# ROLETA2-A1-P01.net
KiCad netlist of a schematic drawn in Altium Designer
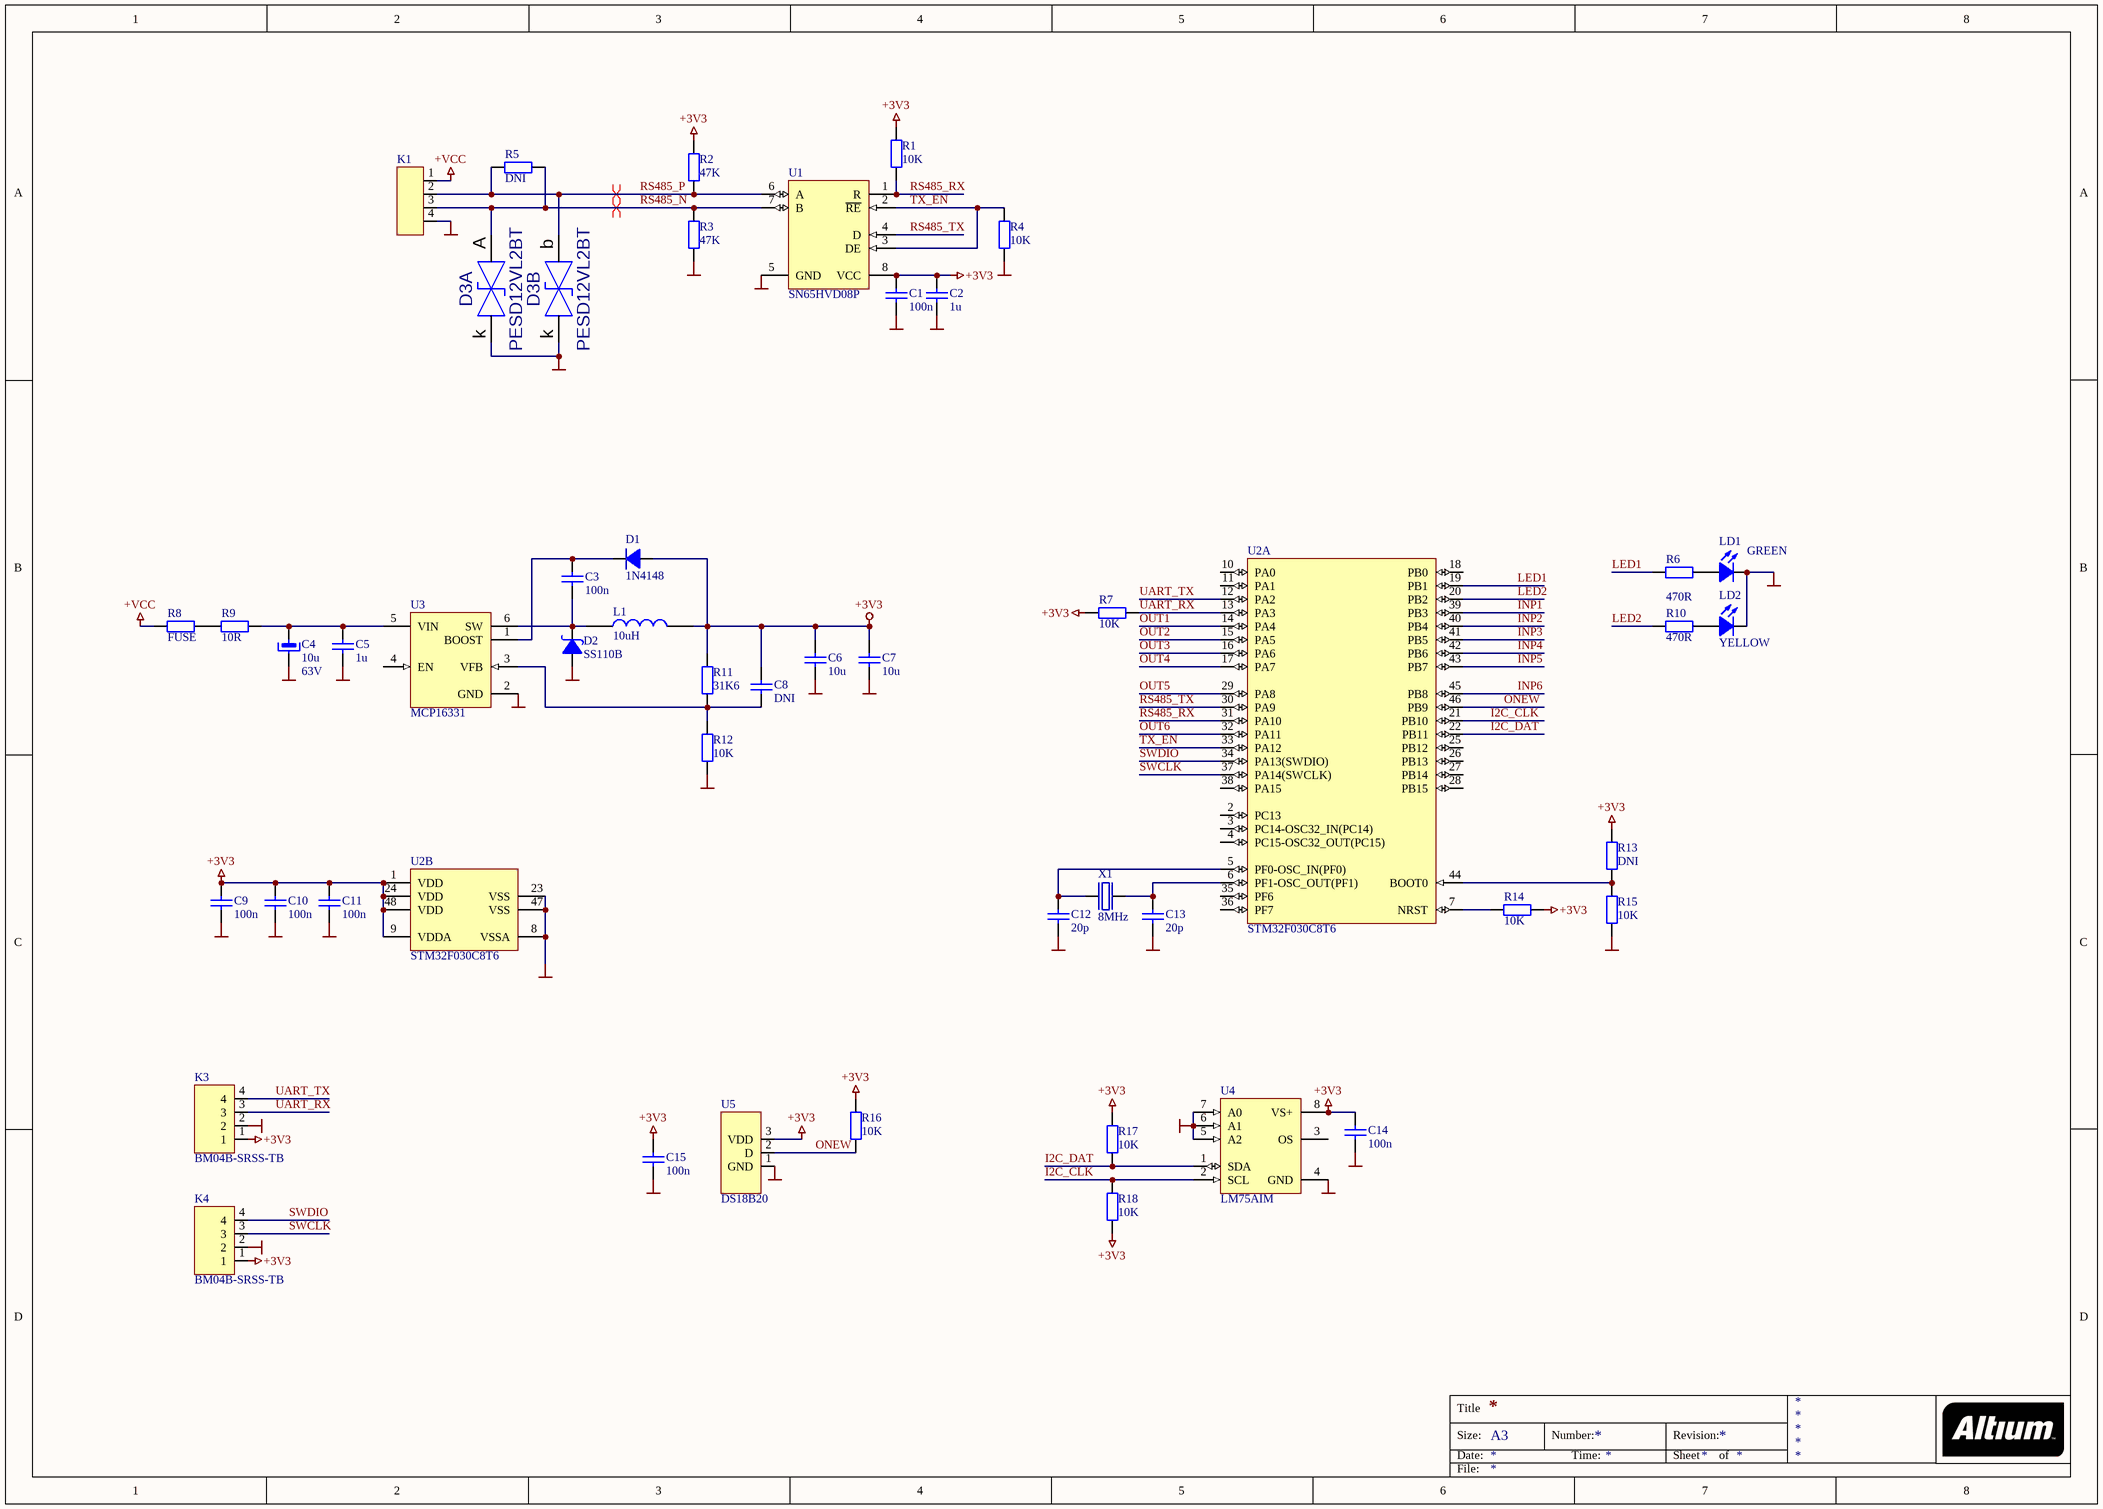
[diagram p0: ROLETA2-A1-P01.SchDoc]

(export (version "E")
  (design (tool "Eeschema 10.0.6"))
  (components
    (comp (ref "C1")
      (value "100n")
      (footprint "Passive:CC0805-1")
      (description "Capacitor chip ceramic 0805")
      (libsource (lib "CapChipCer") (part "CAPCC0805_1U50VX7R"))
    )
    (comp (ref "C2")
      (value "1u")
      (footprint "Passive:CC0805-1")
      (description "Capacitor chip ceramic 0805")
      (libsource (lib "CapChipCer") (part "CAPCC0805_1U50VX7R"))
    )
    (comp (ref "C3")
      (value "100n")
      (footprint "Passive:CC0805-1")
      (description "Capacitor chip ceramic 0805")
      (libsource (lib "CapChipCer") (part "CAPCC0805_1U50VX7R"))
    )
    (comp (ref "C4")
      (value "10u")
      (footprint "CAPPS-D6.3X7.7")
      (description "Capacitor electrolitic SMD 6.3X6.3X7.7MM low ESR")
      (fields (field (name "COMMENT2") "63V"))
      (libsource (lib "CapElectTht") (part "CAPPS100U25VFP"))
    )
    (comp (ref "C5")
      (value "1u")
      (footprint "Passive:CC0805-1")
      (description "Capacitor chip ceramic 0805")
      (libsource (lib "CapChipCer") (part "CAPCC0805_1U50VX7R"))
    )
    (comp (ref "C6")
      (value "10u")
      (footprint "CC0805-1")
      (description "Capacitor chip ceramic 0805")
      (libsource (lib "CapChipCer") (part "CAPCC0805_10U16VX5R"))
    )
    (comp (ref "C7")
      (value "10u")
      (footprint "CC0805-1")
      (description "Capacitor chip ceramic 0805")
      (libsource (lib "CapChipCer") (part "CAPCC0805_10U16VX5R"))
    )
    (comp (ref "C8")
      (value "DNI")
      (footprint "Passive:CC0805-1")
      (description "Capacitor chip ceramic 0805")
      (libsource (lib "CapChipCer") (part "CAPCC0805_1U50VX7R"))
    )
    (comp (ref "C9")
      (value "100n")
      (footprint "CC0805-1")
      (description "Capacitor chip ceramic 0805")
      (libsource (lib "CapChipCer") (part "CAPCC0805_100N50VX7R"))
    )
    (comp (ref "C10")
      (value "100n")
      (footprint "CC0805-1")
      (description "Capacitor chip ceramic 0805")
      (libsource (lib "CapChipCer") (part "CAPCC0805_100N50VX7R"))
    )
    (comp (ref "C11")
      (value "100n")
      (footprint "CC0805-1")
      (description "Capacitor chip ceramic 0805")
      (libsource (lib "CapChipCer") (part "CAPCC0805_100N50VX7R"))
    )
    (comp (ref "C12")
      (value "20p")
      (footprint "CC0805-1")
      (description "Capacitor chip ceramic 0805")
      (libsource (lib "CapChipCer") (part "CAPCC0805_100N50VX7R"))
    )
    (comp (ref "C13")
      (value "20p")
      (footprint "CC0805-1")
      (description "Capacitor chip ceramic 0805")
      (libsource (lib "CapChipCer") (part "CAPCC0805_100N50VX7R"))
    )
    (comp (ref "C14")
      (value "100n")
      (footprint "CC0805-1")
      (description "Capacitor chip ceramic 0805")
      (libsource (lib "CapChipCer") (part "CAPCC0805_100N50VX7R"))
    )
    (comp (ref "C15")
      (value "100n")
      (footprint "CC0805-1")
      (description "Capacitor chip ceramic 0805")
      (libsource (lib "CapChipCer") (part "CAPCC0805_100N50VX7R"))
    )
    (comp (ref "D1")
      (value "1N4148")
      (footprint "Active:SOD323")
      (description "Small Signal Diode")
      (fields (field (name "MANUFACTURER") "Vishay"))
      (libsource (lib "Discrete") (part "D-1N4148WS"))
    )
    (comp (ref "D2")
      (value "SS110B")
      (footprint "Passive:DO-214AC")
      (description "Schottky Diode")
      (fields (field (name "MANUFACTURER") "multicomp"))
      (libsource (lib "Discrete") (part "CD214A-B240LF-0.3V@1A"))
    )
    (comp (ref "D3")
      (value "PESD12VL2BT")
      (footprint "SOT-23_NUP2105L(Primary)")
      (description "Diode")
      (libsource (lib "fractal_lib") (part "NUP2105L"))
    )
    (comp (ref "K1")
      (value "Terminal Block Connector, 3.81mm, Right Angle")
      (footprint "CONN_3.81_4")
      (description "Terminal Block Connector, 3.81mm, 4pin")
      (libsource (lib "fractal_lib") (part "CONN_TB_3.81_4PIN"))
    )
    (comp (ref "K3")
      (value "BM04B-SRSS-TB")
      (footprint "JST-SH-4pin")
      (description "JST connector 4pin vertical")
      (libsource (lib "fractal_lib") (part "JST-SH-BM04B-SRSS-TB"))
    )
    (comp (ref "K4")
      (value "BM04B-SRSS-TB")
      (footprint "JST-SH-4pin")
      (description "JST connector 4pin vertical")
      (libsource (lib "fractal_lib") (part "JST-SH-BM04B-SRSS-TB"))
    )
    (comp (ref "L1")
      (value "10uH")
      (footprint "IND-LQH32CN4R7M33l")
      (description "Chip Inductor 4 x 4 mm")
      (fields (field (name "MANUFACTURER") "Murata"))
      (libsource (lib "Induct") (part "LQH44PN100MP0L"))
    )
    (comp (ref "LD1")
      (value "GREEN")
      (footprint "Active:LEDGREENC190")
      (description "LED green HSMG vertical")
      (fields (field (name "MANUFACTURER") "Avago"))
      (libsource (lib "Discrete") (part "LED-GREEN0603V"))
    )
    (comp (ref "LD2")
      (value "YELLOW")
      (footprint "Active:LEDYELLOWC190")
      (description "LED yellow HSMY vertical")
      (fields (field (name "MANUFACTURER") "Avago"))
      (libsource (lib "Discrete") (part "LED-YELLOW0603V"))
    )
    (comp (ref "R1")
      (value "10K")
      (footprint "RC0805-1")
      (description "Chip Resistor 0805")
      (libsource (lib "") (part "RES0805_1"))
    )
    (comp (ref "R2")
      (value "47K")
      (footprint "RC0805-1")
      (description "Chip Resistor 0805")
      (libsource (lib "Resistors") (part "RES0805"))
    )
    (comp (ref "R3")
      (value "47K")
      (footprint "RC0805-1")
      (description "Chip Resistor 0805")
      (libsource (lib "Resistors") (part "RES0805"))
    )
    (comp (ref "R4")
      (value "10K")
      (footprint "RC0805-1")
      (description "Chip Resistor 0805")
      (libsource (lib "") (part "RES0805_1"))
    )
    (comp (ref "R5")
      (value "DNI")
      (footprint "RC0805-1")
      (description "Chip Resistor 0805")
      (libsource (lib "") (part "RES0805_1"))
    )
    (comp (ref "R6")
      (value "470R")
      (footprint "RC0805-1")
      (description "Chip Resistor 0805")
      (libsource (lib "") (part "RES0805_1"))
    )
    (comp (ref "R7")
      (value "10K")
      (footprint "RC0805-1")
      (description "Chip Resistor 0805")
      (libsource (lib "") (part "RES0805_1"))
    )
    (comp (ref "R8")
      (value "FUSE")
      (footprint "RC1206-1")
      (description "Chip Resistor 1206")
      (libsource (lib "Resistors") (part "RES1206"))
    )
    (comp (ref "R9")
      (value "10R")
      (footprint "RC0805-1")
      (description "Chip Resistor 0805")
      (libsource (lib "") (part "RES0805_3"))
    )
    (comp (ref "R10")
      (value "470R")
      (footprint "RC0805-1")
      (description "Chip Resistor 0805")
      (libsource (lib "") (part "RES0805_1"))
    )
    (comp (ref "R11")
      (value "31K6")
      (footprint "RC0805-1")
      (description "Chip Resistor 0805")
      (libsource (lib "Resistors") (part "RES0805"))
    )
    (comp (ref "R12")
      (value "10K")
      (footprint "RC0805-1")
      (description "Chip Resistor 0805")
      (libsource (lib "Resistors") (part "RES0805"))
    )
    (comp (ref "R13")
      (value "DNI")
      (footprint "RC0805-1")
      (description "Chip Resistor 0805")
      (libsource (lib "Resistors") (part "RES0805"))
    )
    (comp (ref "R14")
      (value "10K")
      (footprint "RC0805-1")
      (description "Chip Resistor 0805")
      (libsource (lib "") (part "RES0805_3"))
    )
    (comp (ref "R15")
      (value "10K")
      (footprint "RC0805-1")
      (description "Chip Resistor 0805")
      (libsource (lib "") (part "RES0805_2"))
    )
    (comp (ref "R16")
      (value "10K")
      (footprint "RC0805-1")
      (description "Chip Resistor 0805")
      (libsource (lib "") (part "RES0805_2"))
    )
    (comp (ref "R17")
      (value "10K")
      (footprint "RC0805-1")
      (description "Chip Resistor 0805")
      (libsource (lib "") (part "RES0805_2"))
    )
    (comp (ref "R18")
      (value "10K")
      (footprint "RC0805-1")
      (description "Chip Resistor 0805")
      (libsource (lib "Resistors") (part "RES0805"))
    )
    (comp (ref "U1")
      (value "SN65HVD08P")
      (footprint "P8")
      (description "3.3 / 5 V RS-485 Transceiver, 10 Mbps, Half Duplex, -40 to 85 degC, 8-pin PDIP (P), Pb-Free (RoHS)")
      (fields (field (name "MANUFACTURER") "Texas Instruments"))
      (libsource (lib "fractal_lib") (part "SN65HVD08P"))
    )
    (comp (ref "U2")
      (value "STM32F030C8T6")
      (footprint "STM-LQFP48_N")
      (libsource (lib "fractal_lib") (part "STM32F030C8T6"))
    )
    (comp (ref "U3")
      (value "MCP16331")
      (footprint "MCHP-SOT-23-CH6_N")
      (fields (field (name "MANUFACTURER") "Microchip") (field (name "PARTNUMBER") "MCP16301T-E/CH"))
      (libsource (lib "fractal_lib") (part "MCP16301T-E/CH"))
    )
    (comp (ref "U4")
      (value "LM75AIM")
      (footprint "M08A_N")
      (description "Digital Temperature Sensor and Thermal Watchdog with Two-Wire Interface, 8-pin Narrow SOIC")
      (fields (field (name "MANUFACTURER") "National Semiconductor"))
      (libsource (lib "fractal_lib") (part "LM75AIM"))
    )
    (comp (ref "U5")
      (value "DS18B20")
      (footprint "TO92")
      (description "digital temperature sensor")
      (libsource (lib "fractal_lib") (part "DS18B20"))
    )
    (comp (ref "X1")
      (value "8MHz")
      (footprint "OSCCC150X320X9-2N")
      (description "SMD Crystal 8MHz")
      (libsource (lib "fractal_lib") (part "XTAL-SMD_8MHz"))
    )
  )
  (nets
    (net (code "1") (name "+3V3") (class "Default")
      (node (ref "C1") (pin "2") (pinfunction "2_2") (pintype "passive"))
      (node (ref "C10") (pin "2") (pinfunction "2_2") (pintype "passive"))
      (node (ref "C11") (pin "2") (pinfunction "2_2") (pintype "passive"))
      (node (ref "C14") (pin "2") (pinfunction "2_2") (pintype "passive"))
      (node (ref "C15") (pin "2") (pinfunction "2_2") (pintype "passive"))
      (node (ref "C2") (pin "2") (pinfunction "2_2") (pintype "passive"))
      (node (ref "C6") (pin "2") (pinfunction "2_2") (pintype "passive"))
      (node (ref "C7") (pin "2") (pinfunction "2_2") (pintype "passive"))
      (node (ref "C8") (pin "2") (pinfunction "2_2") (pintype "passive"))
      (node (ref "C9") (pin "2") (pinfunction "2_2") (pintype "passive"))
      (node (ref "D1") (pin "2") (pinfunction "A_2") (pintype "passive"))
      (node (ref "K3") (pin "1") (pinfunction "1_1") (pintype "passive"))
      (node (ref "K4") (pin "1") (pinfunction "1_1") (pintype "passive"))
      (node (ref "L1") (pin "2") (pinfunction "2_2") (pintype "passive"))
      (node (ref "R1") (pin "2") (pinfunction "2_2") (pintype "passive"))
      (node (ref "R11") (pin "2") (pinfunction "2_2") (pintype "passive"))
      (node (ref "R13") (pin "2") (pinfunction "2_2") (pintype "passive"))
      (node (ref "R14") (pin "1") (pinfunction "1_1") (pintype "passive"))
      (node (ref "R16") (pin "1") (pinfunction "1_1") (pintype "passive"))
      (node (ref "R17") (pin "1") (pinfunction "1_1") (pintype "passive"))
      (node (ref "R18") (pin "1") (pinfunction "1_1") (pintype "passive"))
      (node (ref "R2") (pin "2") (pinfunction "2_2") (pintype "passive"))
      (node (ref "R7") (pin "1") (pinfunction "1_1") (pintype "passive"))
      (node (ref "U1") (pin "8") (pinfunction "VCC_8") (pintype "power_in"))
      (node (ref "U2") (pin "1") (pinfunction "VDD_1") (pintype "power_in"))
      (node (ref "U2") (pin "24") (pinfunction "VDD_24") (pintype "power_in"))
      (node (ref "U2") (pin "48") (pinfunction "VDD_48") (pintype "power_in"))
      (node (ref "U2") (pin "9") (pinfunction "VDDA_9") (pintype "power_in"))
      (node (ref "U4") (pin "8") (pinfunction "VS+_8") (pintype "power_in"))
      (node (ref "U5") (pin "3") (pinfunction "VDD_3") (pintype "passive"))
    )
    (net (code "2") (name "+VCC") (class "Default")
      (node (ref "K1") (pin "1") (pinfunction "A_1") (pintype "passive"))
      (node (ref "R8") (pin "1") (pinfunction "1_1") (pintype "passive"))
    )
    (net (code "3") (name "/I2C_CLK") (class "Default")
      (node (ref "R18") (pin "2") (pinfunction "2_2") (pintype "passive"))
      (node (ref "U2") (pin "21") (pinfunction "PB10_21") (pintype "bidirectional"))
      (node (ref "U4") (pin "2") (pinfunction "SCL_2") (pintype "input"))
    )
    (net (code "4") (name "/I2C_DAT") (class "Default")
      (node (ref "R17") (pin "2") (pinfunction "2_2") (pintype "passive"))
      (node (ref "U2") (pin "22") (pinfunction "PB11_22") (pintype "bidirectional"))
      (node (ref "U4") (pin "1") (pinfunction "SDA_1") (pintype "bidirectional"))
    )
    (net (code "5") (name "/INP1") (class "Default")
      (node (ref "U2") (pin "39") (pinfunction "PB3_39") (pintype "bidirectional"))
    )
    (net (code "6") (name "/INP2") (class "Default")
      (node (ref "U2") (pin "40") (pinfunction "PB4_40") (pintype "bidirectional"))
    )
    (net (code "7") (name "/INP3") (class "Default")
      (node (ref "U2") (pin "41") (pinfunction "PB5_41") (pintype "bidirectional"))
    )
    (net (code "8") (name "/INP4") (class "Default")
      (node (ref "U2") (pin "42") (pinfunction "PB6_42") (pintype "bidirectional"))
    )
    (net (code "9") (name "/INP5") (class "Default")
      (node (ref "U2") (pin "43") (pinfunction "PB7_43") (pintype "bidirectional"))
    )
    (net (code "10") (name "/INP6") (class "Default")
      (node (ref "U2") (pin "45") (pinfunction "PB8_45") (pintype "bidirectional"))
    )
    (net (code "11") (name "/LED1") (class "Default")
      (node (ref "R6") (pin "1") (pinfunction "1_1") (pintype "passive"))
      (node (ref "U2") (pin "19") (pinfunction "PB1_19") (pintype "bidirectional"))
    )
    (net (code "12") (name "/LED2") (class "Default")
      (node (ref "R10") (pin "1") (pinfunction "1_1") (pintype "passive"))
      (node (ref "U2") (pin "20") (pinfunction "PB2_20") (pintype "bidirectional"))
    )
    (net (code "13") (name "/ONEW") (class "Default")
      (node (ref "R16") (pin "2") (pinfunction "2_2") (pintype "passive"))
      (node (ref "U2") (pin "46") (pinfunction "PB9_46") (pintype "bidirectional"))
      (node (ref "U5") (pin "2") (pinfunction "D_2") (pintype "passive"))
    )
    (net (code "14") (name "/OUT1") (class "Default")
      (node (ref "U2") (pin "14") (pinfunction "PA4_14") (pintype "bidirectional"))
    )
    (net (code "15") (name "/OUT2") (class "Default")
      (node (ref "U2") (pin "15") (pinfunction "PA5_15") (pintype "bidirectional"))
    )
    (net (code "16") (name "/OUT3") (class "Default")
      (node (ref "U2") (pin "16") (pinfunction "PA6_16") (pintype "bidirectional"))
    )
    (net (code "17") (name "/OUT4") (class "Default")
      (node (ref "U2") (pin "17") (pinfunction "PA7_17") (pintype "bidirectional"))
    )
    (net (code "18") (name "/OUT5") (class "Default")
      (node (ref "U2") (pin "29") (pinfunction "PA8_29") (pintype "bidirectional"))
    )
    (net (code "19") (name "/OUT6") (class "Default")
      (node (ref "U2") (pin "32") (pinfunction "PA11_32") (pintype "bidirectional"))
    )
    (net (code "20") (name "/RS485_N") (class "Default")
      (node (ref "D3") (pin "A") (pinfunction "A_A") (pintype "passive"))
      (node (ref "K1") (pin "3") (pinfunction "A_3") (pintype "passive"))
      (node (ref "R3") (pin "2") (pinfunction "2_2") (pintype "passive"))
      (node (ref "R5") (pin "2") (pinfunction "2_2") (pintype "passive"))
      (node (ref "U1") (pin "7") (pinfunction "B_7") (pintype "bidirectional"))
    )
    (net (code "21") (name "/RS485_P") (class "Default")
      (node (ref "D3") (pin "b") (pinfunction "A_b") (pintype "passive"))
      (node (ref "K1") (pin "2") (pinfunction "K_2") (pintype "passive"))
      (node (ref "R2") (pin "1") (pinfunction "1_1") (pintype "passive"))
      (node (ref "R5") (pin "1") (pinfunction "1_1") (pintype "passive"))
      (node (ref "U1") (pin "6") (pinfunction "A_6") (pintype "bidirectional"))
    )
    (net (code "22") (name "/RS485_RX") (class "Default")
      (node (ref "R1") (pin "1") (pinfunction "1_1") (pintype "passive"))
      (node (ref "U1") (pin "1") (pinfunction "R_1") (pintype "tri_state"))
      (node (ref "U2") (pin "31") (pinfunction "PA10_31") (pintype "bidirectional"))
    )
    (net (code "23") (name "/RS485_TX") (class "Default")
      (node (ref "U1") (pin "4") (pinfunction "D_4") (pintype "input"))
      (node (ref "U2") (pin "30") (pinfunction "PA9_30") (pintype "bidirectional"))
    )
    (net (code "24") (name "/SWCLK") (class "Default")
      (node (ref "K4") (pin "3") (pinfunction "3_3") (pintype "passive"))
      (node (ref "U2") (pin "37") (pinfunction "PA14(SWCLK)_37") (pintype "bidirectional"))
    )
    (net (code "25") (name "/SWDIO") (class "Default")
      (node (ref "K4") (pin "4") (pinfunction "4_4") (pintype "passive"))
      (node (ref "U2") (pin "34") (pinfunction "PA13(SWDIO)_34") (pintype "bidirectional"))
    )
    (net (code "26") (name "/TX_EN") (class "Default")
      (node (ref "R4") (pin "2") (pinfunction "2_2") (pintype "passive"))
      (node (ref "U1") (pin "2") (pinfunction "~{RE}_2") (pintype "input"))
      (node (ref "U1") (pin "3") (pinfunction "DE_3") (pintype "input"))
      (node (ref "U2") (pin "33") (pinfunction "PA12_33") (pintype "bidirectional"))
    )
    (net (code "27") (name "/UART_RX") (class "Default")
      (node (ref "K3") (pin "3") (pinfunction "3_3") (pintype "passive"))
      (node (ref "R7") (pin "2") (pinfunction "2_2") (pintype "passive"))
      (node (ref "U2") (pin "13") (pinfunction "PA3_13") (pintype "bidirectional"))
    )
    (net (code "28") (name "/UART_TX") (class "Default")
      (node (ref "K3") (pin "4") (pinfunction "4_4") (pintype "passive"))
      (node (ref "U2") (pin "12") (pinfunction "PA2_12") (pintype "bidirectional"))
    )
    (net (code "29") (name "GND") (class "Default")
      (node (ref "C1") (pin "1") (pinfunction "1_1") (pintype "passive"))
      (node (ref "C10") (pin "1") (pinfunction "1_1") (pintype "passive"))
      (node (ref "C11") (pin "1") (pinfunction "1_1") (pintype "passive"))
      (node (ref "C12") (pin "1") (pinfunction "1_1") (pintype "passive"))
      (node (ref "C13") (pin "1") (pinfunction "1_1") (pintype "passive"))
      (node (ref "C14") (pin "1") (pinfunction "1_1") (pintype "passive"))
      (node (ref "C15") (pin "1") (pinfunction "1_1") (pintype "passive"))
      (node (ref "C2") (pin "1") (pinfunction "1_1") (pintype "passive"))
      (node (ref "C4") (pin "2") (pinfunction "2_2") (pintype "passive"))
      (node (ref "C5") (pin "1") (pinfunction "1_1") (pintype "passive"))
      (node (ref "C6") (pin "1") (pinfunction "1_1") (pintype "passive"))
      (node (ref "C7") (pin "1") (pinfunction "1_1") (pintype "passive"))
      (node (ref "C9") (pin "1") (pinfunction "1_1") (pintype "passive"))
      (node (ref "D2") (pin "A") (pinfunction "A_A") (pintype "passive"))
      (node (ref "D3") (pin "k") (pinfunction "K_k") (pintype "power_in"))
      (node (ref "K1") (pin "4") (pinfunction "K_4") (pintype "passive"))
      (node (ref "K3") (pin "2") (pinfunction "2_2") (pintype "passive"))
      (node (ref "K4") (pin "2") (pinfunction "2_2") (pintype "passive"))
      (node (ref "LD1") (pin "1") (pinfunction "C_1") (pintype "passive"))
      (node (ref "LD2") (pin "1") (pinfunction "C_1") (pintype "passive"))
      (node (ref "R12") (pin "1") (pinfunction "1_1") (pintype "passive"))
      (node (ref "R15") (pin "2") (pinfunction "2_2") (pintype "passive"))
      (node (ref "R3") (pin "1") (pinfunction "1_1") (pintype "passive"))
      (node (ref "R4") (pin "1") (pinfunction "1_1") (pintype "passive"))
      (node (ref "U1") (pin "5") (pinfunction "GND_5") (pintype "power_in"))
      (node (ref "U2") (pin "23") (pinfunction "VSS_23") (pintype "power_in"))
      (node (ref "U2") (pin "47") (pinfunction "VSS_47") (pintype "power_in"))
      (node (ref "U2") (pin "8") (pinfunction "VSSA_8") (pintype "power_in"))
      (node (ref "U3") (pin "2") (pinfunction "GND_2") (pintype "power_in"))
      (node (ref "U4") (pin "4") (pinfunction "GND_4") (pintype "power_in"))
      (node (ref "U4") (pin "5") (pinfunction "A2_5") (pintype "input"))
      (node (ref "U4") (pin "6") (pinfunction "A1_6") (pintype "input"))
      (node (ref "U4") (pin "7") (pinfunction "A0_7") (pintype "input"))
      (node (ref "U5") (pin "1") (pinfunction "GND_1") (pintype "passive"))
    )
    (net (code "30") (name "Net-(D1-C)") (class "Default")
      (node (ref "C3") (pin "2") (pinfunction "2_2") (pintype "passive"))
      (node (ref "D1") (pin "1") (pinfunction "C_1") (pintype "passive"))
      (node (ref "U3") (pin "1") (pinfunction "BOOST_1") (pintype "power_in"))
    )
    (net (code "31") (name "Net-(LD1-A)") (class "Default")
      (node (ref "LD1") (pin "2") (pinfunction "A_2") (pintype "passive"))
      (node (ref "R6") (pin "2") (pinfunction "2_2") (pintype "passive"))
    )
    (net (code "32") (name "Net-(LD2-A)") (class "Default")
      (node (ref "LD2") (pin "2") (pinfunction "A_2") (pintype "passive"))
      (node (ref "R10") (pin "2") (pinfunction "2_2") (pintype "passive"))
    )
    (net (code "33") (name "Net-(R8-Pad2)") (class "Default")
      (node (ref "R8") (pin "2") (pinfunction "2_2") (pintype "passive"))
      (node (ref "R9") (pin "2") (pinfunction "2_2") (pintype "passive"))
    )
    (net (code "34") (name "Net-(U2A-BOOT0)") (class "Default")
      (node (ref "R13") (pin "1") (pinfunction "1_1") (pintype "passive"))
      (node (ref "R15") (pin "1") (pinfunction "1_1") (pintype "passive"))
      (node (ref "U2") (pin "44") (pinfunction "BOOT0_44") (pintype "input"))
    )
    (net (code "35") (name "Net-(U2A-NRST)") (class "Default")
      (node (ref "R14") (pin "2") (pinfunction "2_2") (pintype "passive"))
      (node (ref "U2") (pin "7") (pinfunction "NRST_7") (pintype "bidirectional"))
    )
    (net (code "36") (name "Net-(U2A-PF0-OSC_IN(PF0))") (class "Default")
      (node (ref "C12") (pin "2") (pinfunction "2_2") (pintype "passive"))
      (node (ref "U2") (pin "5") (pinfunction "PF0-OSC_IN(PF0)_5") (pintype "bidirectional"))
      (node (ref "X1") (pin "1") (pinfunction "OUT_1") (pintype "power_in"))
    )
    (net (code "37") (name "Net-(U2A-PF1-OSC_OUT(PF1))") (class "Default")
      (node (ref "C13") (pin "2") (pinfunction "2_2") (pintype "passive"))
      (node (ref "U2") (pin "6") (pinfunction "PF1-OSC_OUT(PF1)_6") (pintype "bidirectional"))
      (node (ref "X1") (pin "2") (pinfunction "IN_2") (pintype "passive"))
    )
    (net (code "38") (name "Net-(U3-SW)") (class "Default")
      (node (ref "C3") (pin "1") (pinfunction "1_1") (pintype "passive"))
      (node (ref "D2") (pin "K") (pinfunction "K_K") (pintype "passive"))
      (node (ref "L1") (pin "1") (pinfunction "1_1") (pintype "passive"))
      (node (ref "U3") (pin "6") (pinfunction "SW_6") (pintype "power_in"))
    )
    (net (code "39") (name "Net-(U3-VFB)") (class "Default")
      (node (ref "C8") (pin "1") (pinfunction "1_1") (pintype "passive"))
      (node (ref "R11") (pin "1") (pinfunction "1_1") (pintype "passive"))
      (node (ref "R12") (pin "2") (pinfunction "2_2") (pintype "passive"))
      (node (ref "U3") (pin "3") (pinfunction "VFB_3") (pintype "input"))
    )
    (net (code "40") (name "Net-(U3-VIN)") (class "Default")
      (node (ref "C4") (pin "1") (pinfunction "1_1") (pintype "passive"))
      (node (ref "C5") (pin "2") (pinfunction "2_2") (pintype "passive"))
      (node (ref "R9") (pin "1") (pinfunction "1_1") (pintype "passive"))
      (node (ref "U3") (pin "5") (pinfunction "VIN_5") (pintype "power_in"))
    )
    (net (code "41") (name "unconnected-(U2A-PA0-Pad10)") (class "Default")
      (node (ref "U2") (pin "10") (pinfunction "PA0_10") (pintype "bidirectional"))
    )
    (net (code "42") (name "unconnected-(U2A-PA1-Pad11)") (class "Default")
      (node (ref "U2") (pin "11") (pinfunction "PA1_11") (pintype "bidirectional"))
    )
    (net (code "43") (name "unconnected-(U2A-PA15-Pad38)") (class "Default")
      (node (ref "U2") (pin "38") (pinfunction "PA15_38") (pintype "bidirectional"))
    )
    (net (code "44") (name "unconnected-(U2A-PB0-Pad18)") (class "Default")
      (node (ref "U2") (pin "18") (pinfunction "PB0_18") (pintype "bidirectional"))
    )
    (net (code "45") (name "unconnected-(U2A-PB12-Pad25)") (class "Default")
      (node (ref "U2") (pin "25") (pinfunction "PB12_25") (pintype "bidirectional"))
    )
    (net (code "46") (name "unconnected-(U2A-PB13-Pad26)") (class "Default")
      (node (ref "U2") (pin "26") (pinfunction "PB13_26") (pintype "bidirectional"))
    )
    (net (code "47") (name "unconnected-(U2A-PB14-Pad27)") (class "Default")
      (node (ref "U2") (pin "27") (pinfunction "PB14_27") (pintype "bidirectional"))
    )
    (net (code "48") (name "unconnected-(U2A-PB15-Pad28)") (class "Default")
      (node (ref "U2") (pin "28") (pinfunction "PB15_28") (pintype "bidirectional"))
    )
    (net (code "49") (name "unconnected-(U2A-PC13-Pad2)") (class "Default")
      (node (ref "U2") (pin "2") (pinfunction "PC13_2") (pintype "bidirectional"))
    )
    (net (code "50") (name "unconnected-(U2A-PC14-OSC32_IN(PC14)-Pad3)") (class "Default")
      (node (ref "U2") (pin "3") (pinfunction "PC14-OSC32_IN(PC14)_3") (pintype "bidirectional"))
    )
    (net (code "51") (name "unconnected-(U2A-PC15-OSC32_OUT(PC15)-Pad4)") (class "Default")
      (node (ref "U2") (pin "4") (pinfunction "PC15-OSC32_OUT(PC15)_4") (pintype "bidirectional"))
    )
    (net (code "52") (name "unconnected-(U2A-PF6-Pad35)") (class "Default")
      (node (ref "U2") (pin "35") (pinfunction "PF6_35") (pintype "bidirectional"))
    )
    (net (code "53") (name "unconnected-(U2A-PF7-Pad36)") (class "Default")
      (node (ref "U2") (pin "36") (pinfunction "PF7_36") (pintype "bidirectional"))
    )
    (net (code "54") (name "unconnected-(U3-EN-Pad4)") (class "Default")
      (node (ref "U3") (pin "4") (pinfunction "EN_4") (pintype "input"))
    )
    (net (code "55") (name "unconnected-(U4-OS-Pad3)") (class "Default")
      (node (ref "U4") (pin "3") (pinfunction "OS_3") (pintype "open_collector"))
    )
  )
)
